# ColourBreakout.net
KiCad netlist of a schematic drawn in Altium Designer
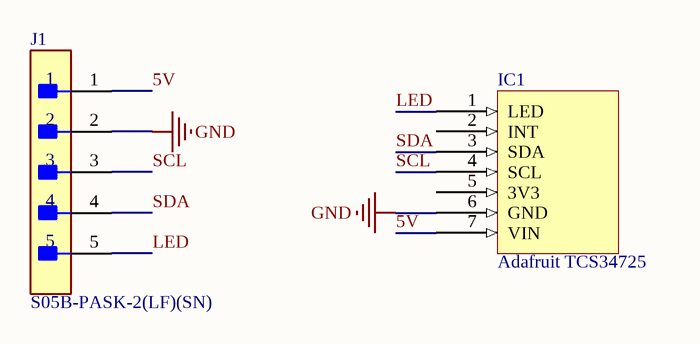
[diagram p0: ColourBreakout.SchDoc]

(export (version "E")
  (design (tool "Eeschema 10.0.6"))
  (components
    (comp (ref "IC1")
      (value "Adafruit TCS34725")
      (footprint "Adafruit TCS34725-Footprint-1")
      (libsource (lib "Jouveer") (part "Adafruit TCS34725-Symbol-1"))
    )
    (comp (ref "J1")
      (value "S05B-PASK-2(LF)(SN)")
      (footprint "FP-S05B-PASK-2_LF_SN-MFG")
      (description "CONN HEADER R/A 5POS 2MM")
      (libsource (lib "Altium Content Vault") (part "bf93c07fd2649a848d0ec8585582aab"))
    )
  )
  (nets
    (net (code "1") (name "/5V") (class "Default")
      (node (ref "IC1") (pin "7") (pinfunction "VIN_7") (pintype "input"))
      (node (ref "J1") (pin "1") (pinfunction "1_1") (pintype "passive"))
    )
    (net (code "2") (name "/LED") (class "Default")
      (node (ref "IC1") (pin "1") (pinfunction "LED_1") (pintype "input"))
      (node (ref "J1") (pin "5") (pinfunction "5_5") (pintype "passive"))
    )
    (net (code "3") (name "/SCL") (class "Default")
      (node (ref "IC1") (pin "4") (pinfunction "SCL_4") (pintype "input"))
      (node (ref "J1") (pin "3") (pinfunction "3_3") (pintype "passive"))
    )
    (net (code "4") (name "/SDA") (class "Default")
      (node (ref "IC1") (pin "3") (pinfunction "SDA_3") (pintype "input"))
      (node (ref "J1") (pin "4") (pinfunction "4_4") (pintype "passive"))
    )
    (net (code "5") (name "GND") (class "Default")
      (node (ref "IC1") (pin "6") (pinfunction "GND_6") (pintype "input"))
      (node (ref "J1") (pin "2") (pinfunction "2_2") (pintype "passive"))
    )
    (net (code "6") (name "unconnected-(IC1-3V3-Pad5)") (class "Default")
      (node (ref "IC1") (pin "5") (pinfunction "3V3_5") (pintype "input"))
    )
    (net (code "7") (name "unconnected-(IC1-INT-Pad2)") (class "Default")
      (node (ref "IC1") (pin "2") (pinfunction "INT_2") (pintype "input"))
    )
  )
)
